# BoardConnector.net
KiCad netlist of a schematic drawn in Altium Designer
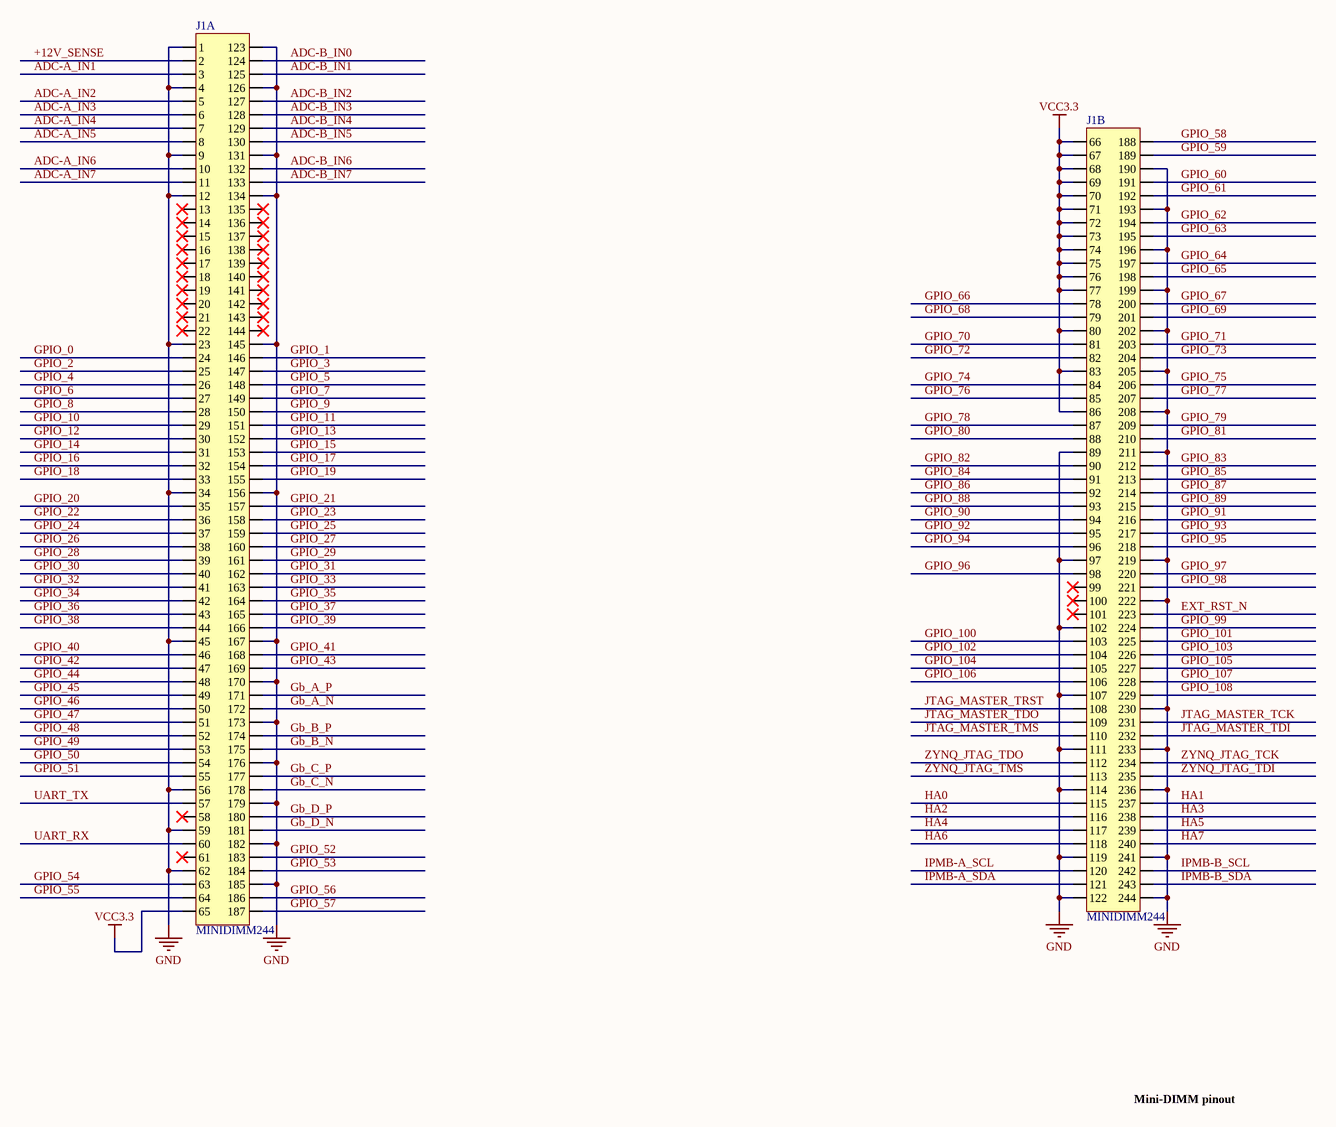
[diagram p0: BoardConnector.SchDoc]

(export (version "E")
  (design (tool "Eeschema 10.0.6"))
  (components
    (comp (ref "J1")
      (value "MINIDIMM244")
      (footprint "miniDIMM244")
      (description "244-pin miniDIMM pads")
      (libsource (lib "CustomParts") (part "MINIDIMM244"))
    )
  )
  (nets
    (net (code "1") (name "/+12V_SENSE") (class "Default")
      (node (ref "J1") (pin "2") (pinfunction "2_2") (pintype "passive"))
    )
    (net (code "2") (name "/ADC-A_IN1") (class "Default")
      (node (ref "J1") (pin "3") (pinfunction "3_3") (pintype "passive"))
    )
    (net (code "3") (name "/ADC-A_IN2") (class "Default")
      (node (ref "J1") (pin "5") (pinfunction "5_5") (pintype "passive"))
    )
    (net (code "4") (name "/ADC-A_IN3") (class "Default")
      (node (ref "J1") (pin "6") (pinfunction "6_6") (pintype "passive"))
    )
    (net (code "5") (name "/ADC-A_IN4") (class "Default")
      (node (ref "J1") (pin "7") (pinfunction "7_7") (pintype "passive"))
    )
    (net (code "6") (name "/ADC-A_IN5") (class "Default")
      (node (ref "J1") (pin "8") (pinfunction "8_8") (pintype "passive"))
    )
    (net (code "7") (name "/ADC-A_IN6") (class "Default")
      (node (ref "J1") (pin "10") (pinfunction "10_10") (pintype "passive"))
    )
    (net (code "8") (name "/ADC-A_IN7") (class "Default")
      (node (ref "J1") (pin "11") (pinfunction "11_11") (pintype "passive"))
    )
    (net (code "9") (name "/ADC-B_IN0") (class "Default")
      (node (ref "J1") (pin "124") (pinfunction "124_124") (pintype "passive"))
    )
    (net (code "10") (name "/ADC-B_IN1") (class "Default")
      (node (ref "J1") (pin "125") (pinfunction "125_125") (pintype "passive"))
    )
    (net (code "11") (name "/ADC-B_IN2") (class "Default")
      (node (ref "J1") (pin "127") (pinfunction "127_127") (pintype "passive"))
    )
    (net (code "12") (name "/ADC-B_IN3") (class "Default")
      (node (ref "J1") (pin "128") (pinfunction "128_128") (pintype "passive"))
    )
    (net (code "13") (name "/ADC-B_IN4") (class "Default")
      (node (ref "J1") (pin "129") (pinfunction "129_129") (pintype "passive"))
    )
    (net (code "14") (name "/ADC-B_IN5") (class "Default")
      (node (ref "J1") (pin "130") (pinfunction "130_130") (pintype "passive"))
    )
    (net (code "15") (name "/ADC-B_IN6") (class "Default")
      (node (ref "J1") (pin "132") (pinfunction "132_132") (pintype "passive"))
    )
    (net (code "16") (name "/ADC-B_IN7") (class "Default")
      (node (ref "J1") (pin "133") (pinfunction "133_133") (pintype "passive"))
    )
    (net (code "17") (name "/EXT_RST_N") (class "Default")
      (node (ref "J1") (pin "223") (pinfunction "223_223") (pintype "passive"))
    )
    (net (code "18") (name "/GPIO_0") (class "Default")
      (node (ref "J1") (pin "24") (pinfunction "24_24") (pintype "passive"))
    )
    (net (code "19") (name "/GPIO_1") (class "Default")
      (node (ref "J1") (pin "146") (pinfunction "146_146") (pintype "passive"))
    )
    (net (code "20") (name "/GPIO_2") (class "Default")
      (node (ref "J1") (pin "25") (pinfunction "25_25") (pintype "passive"))
    )
    (net (code "21") (name "/GPIO_3") (class "Default")
      (node (ref "J1") (pin "147") (pinfunction "147_147") (pintype "passive"))
    )
    (net (code "22") (name "/GPIO_4") (class "Default")
      (node (ref "J1") (pin "26") (pinfunction "26_26") (pintype "passive"))
    )
    (net (code "23") (name "/GPIO_5") (class "Default")
      (node (ref "J1") (pin "148") (pinfunction "148_148") (pintype "passive"))
    )
    (net (code "24") (name "/GPIO_6") (class "Default")
      (node (ref "J1") (pin "27") (pinfunction "27_27") (pintype "passive"))
    )
    (net (code "25") (name "/GPIO_7") (class "Default")
      (node (ref "J1") (pin "149") (pinfunction "149_149") (pintype "passive"))
    )
    (net (code "26") (name "/GPIO_8") (class "Default")
      (node (ref "J1") (pin "28") (pinfunction "28_28") (pintype "passive"))
    )
    (net (code "27") (name "/GPIO_9") (class "Default")
      (node (ref "J1") (pin "150") (pinfunction "150_150") (pintype "passive"))
    )
    (net (code "28") (name "/GPIO_10") (class "Default")
      (node (ref "J1") (pin "29") (pinfunction "29_29") (pintype "passive"))
    )
    (net (code "29") (name "/GPIO_11") (class "Default")
      (node (ref "J1") (pin "151") (pinfunction "151_151") (pintype "passive"))
    )
    (net (code "30") (name "/GPIO_12") (class "Default")
      (node (ref "J1") (pin "30") (pinfunction "30_30") (pintype "passive"))
    )
    (net (code "31") (name "/GPIO_13") (class "Default")
      (node (ref "J1") (pin "152") (pinfunction "152_152") (pintype "passive"))
    )
    (net (code "32") (name "/GPIO_14") (class "Default")
      (node (ref "J1") (pin "31") (pinfunction "31_31") (pintype "passive"))
    )
    (net (code "33") (name "/GPIO_15") (class "Default")
      (node (ref "J1") (pin "153") (pinfunction "153_153") (pintype "passive"))
    )
    (net (code "34") (name "/GPIO_16") (class "Default")
      (node (ref "J1") (pin "32") (pinfunction "32_32") (pintype "passive"))
    )
    (net (code "35") (name "/GPIO_17") (class "Default")
      (node (ref "J1") (pin "154") (pinfunction "154_154") (pintype "passive"))
    )
    (net (code "36") (name "/GPIO_18") (class "Default")
      (node (ref "J1") (pin "33") (pinfunction "33_33") (pintype "passive"))
    )
    (net (code "37") (name "/GPIO_19") (class "Default")
      (node (ref "J1") (pin "155") (pinfunction "155_155") (pintype "passive"))
    )
    (net (code "38") (name "/GPIO_20") (class "Default")
      (node (ref "J1") (pin "35") (pinfunction "35_35") (pintype "passive"))
    )
    (net (code "39") (name "/GPIO_21") (class "Default")
      (node (ref "J1") (pin "157") (pinfunction "157_157") (pintype "passive"))
    )
    (net (code "40") (name "/GPIO_22") (class "Default")
      (node (ref "J1") (pin "36") (pinfunction "36_36") (pintype "passive"))
    )
    (net (code "41") (name "/GPIO_23") (class "Default")
      (node (ref "J1") (pin "158") (pinfunction "158_158") (pintype "passive"))
    )
    (net (code "42") (name "/GPIO_24") (class "Default")
      (node (ref "J1") (pin "37") (pinfunction "37_37") (pintype "passive"))
    )
    (net (code "43") (name "/GPIO_25") (class "Default")
      (node (ref "J1") (pin "159") (pinfunction "159_159") (pintype "passive"))
    )
    (net (code "44") (name "/GPIO_26") (class "Default")
      (node (ref "J1") (pin "38") (pinfunction "38_38") (pintype "passive"))
    )
    (net (code "45") (name "/GPIO_27") (class "Default")
      (node (ref "J1") (pin "160") (pinfunction "160_160") (pintype "passive"))
    )
    (net (code "46") (name "/GPIO_28") (class "Default")
      (node (ref "J1") (pin "39") (pinfunction "39_39") (pintype "passive"))
    )
    (net (code "47") (name "/GPIO_29") (class "Default")
      (node (ref "J1") (pin "161") (pinfunction "161_161") (pintype "passive"))
    )
    (net (code "48") (name "/GPIO_30") (class "Default")
      (node (ref "J1") (pin "40") (pinfunction "40_40") (pintype "passive"))
    )
    (net (code "49") (name "/GPIO_31") (class "Default")
      (node (ref "J1") (pin "162") (pinfunction "162_162") (pintype "passive"))
    )
    (net (code "50") (name "/GPIO_32") (class "Default")
      (node (ref "J1") (pin "41") (pinfunction "41_41") (pintype "passive"))
    )
    (net (code "51") (name "/GPIO_33") (class "Default")
      (node (ref "J1") (pin "163") (pinfunction "163_163") (pintype "passive"))
    )
    (net (code "52") (name "/GPIO_34") (class "Default")
      (node (ref "J1") (pin "42") (pinfunction "42_42") (pintype "passive"))
    )
    (net (code "53") (name "/GPIO_35") (class "Default")
      (node (ref "J1") (pin "164") (pinfunction "164_164") (pintype "passive"))
    )
    (net (code "54") (name "/GPIO_36") (class "Default")
      (node (ref "J1") (pin "43") (pinfunction "43_43") (pintype "passive"))
    )
    (net (code "55") (name "/GPIO_37") (class "Default")
      (node (ref "J1") (pin "165") (pinfunction "165_165") (pintype "passive"))
    )
    (net (code "56") (name "/GPIO_38") (class "Default")
      (node (ref "J1") (pin "44") (pinfunction "44_44") (pintype "passive"))
    )
    (net (code "57") (name "/GPIO_39") (class "Default")
      (node (ref "J1") (pin "166") (pinfunction "166_166") (pintype "passive"))
    )
    (net (code "58") (name "/GPIO_40") (class "Default")
      (node (ref "J1") (pin "46") (pinfunction "46_46") (pintype "passive"))
    )
    (net (code "59") (name "/GPIO_41") (class "Default")
      (node (ref "J1") (pin "168") (pinfunction "168_168") (pintype "passive"))
    )
    (net (code "60") (name "/GPIO_42") (class "Default")
      (node (ref "J1") (pin "47") (pinfunction "47_47") (pintype "passive"))
    )
    (net (code "61") (name "/GPIO_43") (class "Default")
      (node (ref "J1") (pin "169") (pinfunction "169_169") (pintype "passive"))
    )
    (net (code "62") (name "/GPIO_44") (class "Default")
      (node (ref "J1") (pin "48") (pinfunction "48_48") (pintype "passive"))
    )
    (net (code "63") (name "/GPIO_45") (class "Default")
      (node (ref "J1") (pin "49") (pinfunction "49_49") (pintype "passive"))
    )
    (net (code "64") (name "/GPIO_46") (class "Default")
      (node (ref "J1") (pin "50") (pinfunction "50_50") (pintype "passive"))
    )
    (net (code "65") (name "/GPIO_47") (class "Default")
      (node (ref "J1") (pin "51") (pinfunction "51_51") (pintype "passive"))
    )
    (net (code "66") (name "/GPIO_48") (class "Default")
      (node (ref "J1") (pin "52") (pinfunction "52_52") (pintype "passive"))
    )
    (net (code "67") (name "/GPIO_49") (class "Default")
      (node (ref "J1") (pin "53") (pinfunction "53_53") (pintype "passive"))
    )
    (net (code "68") (name "/GPIO_50") (class "Default")
      (node (ref "J1") (pin "54") (pinfunction "54_54") (pintype "passive"))
    )
    (net (code "69") (name "/GPIO_51") (class "Default")
      (node (ref "J1") (pin "55") (pinfunction "55_55") (pintype "passive"))
    )
    (net (code "70") (name "/GPIO_52") (class "Default")
      (node (ref "J1") (pin "183") (pinfunction "183_183") (pintype "passive"))
    )
    (net (code "71") (name "/GPIO_53") (class "Default")
      (node (ref "J1") (pin "184") (pinfunction "184_184") (pintype "passive"))
    )
    (net (code "72") (name "/GPIO_54") (class "Default")
      (node (ref "J1") (pin "63") (pinfunction "63_63") (pintype "passive"))
    )
    (net (code "73") (name "/GPIO_55") (class "Default")
      (node (ref "J1") (pin "64") (pinfunction "64_64") (pintype "passive"))
    )
    (net (code "74") (name "/GPIO_56") (class "Default")
      (node (ref "J1") (pin "186") (pinfunction "186_186") (pintype "passive"))
    )
    (net (code "75") (name "/GPIO_57") (class "Default")
      (node (ref "J1") (pin "187") (pinfunction "187_187") (pintype "passive"))
    )
    (net (code "76") (name "/GPIO_58") (class "Default")
      (node (ref "J1") (pin "188") (pinfunction "188_188") (pintype "passive"))
    )
    (net (code "77") (name "/GPIO_59") (class "Default")
      (node (ref "J1") (pin "189") (pinfunction "189_189") (pintype "passive"))
    )
    (net (code "78") (name "/GPIO_60") (class "Default")
      (node (ref "J1") (pin "191") (pinfunction "191_191") (pintype "passive"))
    )
    (net (code "79") (name "/GPIO_61") (class "Default")
      (node (ref "J1") (pin "192") (pinfunction "192_192") (pintype "passive"))
    )
    (net (code "80") (name "/GPIO_62") (class "Default")
      (node (ref "J1") (pin "194") (pinfunction "194_194") (pintype "passive"))
    )
    (net (code "81") (name "/GPIO_63") (class "Default")
      (node (ref "J1") (pin "195") (pinfunction "195_195") (pintype "passive"))
    )
    (net (code "82") (name "/GPIO_64") (class "Default")
      (node (ref "J1") (pin "197") (pinfunction "197_197") (pintype "passive"))
    )
    (net (code "83") (name "/GPIO_65") (class "Default")
      (node (ref "J1") (pin "198") (pinfunction "198_198") (pintype "passive"))
    )
    (net (code "84") (name "/GPIO_66") (class "Default")
      (node (ref "J1") (pin "78") (pinfunction "78_78") (pintype "passive"))
    )
    (net (code "85") (name "/GPIO_67") (class "Default")
      (node (ref "J1") (pin "200") (pinfunction "200_200") (pintype "passive"))
    )
    (net (code "86") (name "/GPIO_68") (class "Default")
      (node (ref "J1") (pin "79") (pinfunction "79_79") (pintype "passive"))
    )
    (net (code "87") (name "/GPIO_69") (class "Default")
      (node (ref "J1") (pin "201") (pinfunction "201_201") (pintype "passive"))
    )
    (net (code "88") (name "/GPIO_70") (class "Default")
      (node (ref "J1") (pin "81") (pinfunction "81_81") (pintype "passive"))
    )
    (net (code "89") (name "/GPIO_71") (class "Default")
      (node (ref "J1") (pin "203") (pinfunction "203_203") (pintype "passive"))
    )
    (net (code "90") (name "/GPIO_72") (class "Default")
      (node (ref "J1") (pin "82") (pinfunction "82_82") (pintype "passive"))
    )
    (net (code "91") (name "/GPIO_73") (class "Default")
      (node (ref "J1") (pin "204") (pinfunction "204_204") (pintype "passive"))
    )
    (net (code "92") (name "/GPIO_74") (class "Default")
      (node (ref "J1") (pin "84") (pinfunction "84_84") (pintype "passive"))
    )
    (net (code "93") (name "/GPIO_75") (class "Default")
      (node (ref "J1") (pin "206") (pinfunction "206_206") (pintype "passive"))
    )
    (net (code "94") (name "/GPIO_76") (class "Default")
      (node (ref "J1") (pin "85") (pinfunction "85_85") (pintype "passive"))
    )
    (net (code "95") (name "/GPIO_77") (class "Default")
      (node (ref "J1") (pin "207") (pinfunction "207_207") (pintype "passive"))
    )
    (net (code "96") (name "/GPIO_78") (class "Default")
      (node (ref "J1") (pin "87") (pinfunction "87_87") (pintype "passive"))
    )
    (net (code "97") (name "/GPIO_79") (class "Default")
      (node (ref "J1") (pin "209") (pinfunction "209_209") (pintype "passive"))
    )
    (net (code "98") (name "/GPIO_80") (class "Default")
      (node (ref "J1") (pin "88") (pinfunction "88_88") (pintype "passive"))
    )
    (net (code "99") (name "/GPIO_81") (class "Default")
      (node (ref "J1") (pin "210") (pinfunction "210_210") (pintype "passive"))
    )
    (net (code "100") (name "/GPIO_82") (class "Default")
      (node (ref "J1") (pin "90") (pinfunction "90_90") (pintype "passive"))
    )
    (net (code "101") (name "/GPIO_83") (class "Default")
      (node (ref "J1") (pin "212") (pinfunction "212_212") (pintype "passive"))
    )
    (net (code "102") (name "/GPIO_84") (class "Default")
      (node (ref "J1") (pin "91") (pinfunction "91_91") (pintype "passive"))
    )
    (net (code "103") (name "/GPIO_85") (class "Default")
      (node (ref "J1") (pin "213") (pinfunction "213_213") (pintype "passive"))
    )
    (net (code "104") (name "/GPIO_86") (class "Default")
      (node (ref "J1") (pin "92") (pinfunction "92_92") (pintype "passive"))
    )
    (net (code "105") (name "/GPIO_87") (class "Default")
      (node (ref "J1") (pin "214") (pinfunction "214_214") (pintype "passive"))
    )
    (net (code "106") (name "/GPIO_88") (class "Default")
      (node (ref "J1") (pin "93") (pinfunction "93_93") (pintype "passive"))
    )
    (net (code "107") (name "/GPIO_89") (class "Default")
      (node (ref "J1") (pin "215") (pinfunction "215_215") (pintype "passive"))
    )
    (net (code "108") (name "/GPIO_90") (class "Default")
      (node (ref "J1") (pin "94") (pinfunction "94_94") (pintype "passive"))
    )
    (net (code "109") (name "/GPIO_91") (class "Default")
      (node (ref "J1") (pin "216") (pinfunction "216_216") (pintype "passive"))
    )
    (net (code "110") (name "/GPIO_92") (class "Default")
      (node (ref "J1") (pin "95") (pinfunction "95_95") (pintype "passive"))
    )
    (net (code "111") (name "/GPIO_93") (class "Default")
      (node (ref "J1") (pin "217") (pinfunction "217_217") (pintype "passive"))
    )
    (net (code "112") (name "/GPIO_94") (class "Default")
      (node (ref "J1") (pin "96") (pinfunction "96_96") (pintype "passive"))
    )
    (net (code "113") (name "/GPIO_95") (class "Default")
      (node (ref "J1") (pin "218") (pinfunction "218_218") (pintype "passive"))
    )
    (net (code "114") (name "/GPIO_96") (class "Default")
      (node (ref "J1") (pin "98") (pinfunction "98_98") (pintype "passive"))
    )
    (net (code "115") (name "/GPIO_97") (class "Default")
      (node (ref "J1") (pin "220") (pinfunction "220_220") (pintype "passive"))
    )
    (net (code "116") (name "/GPIO_98") (class "Default")
      (node (ref "J1") (pin "221") (pinfunction "221_221") (pintype "passive"))
    )
    (net (code "117") (name "/GPIO_99") (class "Default")
      (node (ref "J1") (pin "224") (pinfunction "224_224") (pintype "passive"))
    )
    (net (code "118") (name "/GPIO_100") (class "Default")
      (node (ref "J1") (pin "103") (pinfunction "103_103") (pintype "passive"))
    )
    (net (code "119") (name "/GPIO_101") (class "Default")
      (node (ref "J1") (pin "225") (pinfunction "225_225") (pintype "passive"))
    )
    (net (code "120") (name "/GPIO_102") (class "Default")
      (node (ref "J1") (pin "104") (pinfunction "104_104") (pintype "passive"))
    )
    (net (code "121") (name "/GPIO_103") (class "Default")
      (node (ref "J1") (pin "226") (pinfunction "226_226") (pintype "passive"))
    )
    (net (code "122") (name "/GPIO_104") (class "Default")
      (node (ref "J1") (pin "105") (pinfunction "105_105") (pintype "passive"))
    )
    (net (code "123") (name "/GPIO_105") (class "Default")
      (node (ref "J1") (pin "227") (pinfunction "227_227") (pintype "passive"))
    )
    (net (code "124") (name "/GPIO_106") (class "Default")
      (node (ref "J1") (pin "106") (pinfunction "106_106") (pintype "passive"))
    )
    (net (code "125") (name "/GPIO_107") (class "Default")
      (node (ref "J1") (pin "228") (pinfunction "228_228") (pintype "passive"))
    )
    (net (code "126") (name "/GPIO_108") (class "Default")
      (node (ref "J1") (pin "229") (pinfunction "229_229") (pintype "passive"))
    )
    (net (code "127") (name "/Gb_A_N") (class "Default")
      (node (ref "J1") (pin "172") (pinfunction "172_172") (pintype "passive"))
    )
    (net (code "128") (name "/Gb_A_P") (class "Default")
      (node (ref "J1") (pin "171") (pinfunction "171_171") (pintype "passive"))
    )
    (net (code "129") (name "/Gb_B_N") (class "Default")
      (node (ref "J1") (pin "175") (pinfunction "175_175") (pintype "passive"))
    )
    (net (code "130") (name "/Gb_B_P") (class "Default")
      (node (ref "J1") (pin "174") (pinfunction "174_174") (pintype "passive"))
    )
    (net (code "131") (name "/Gb_C_N") (class "Default")
      (node (ref "J1") (pin "178") (pinfunction "178_178") (pintype "passive"))
    )
    (net (code "132") (name "/Gb_C_P") (class "Default")
      (node (ref "J1") (pin "177") (pinfunction "177_177") (pintype "passive"))
    )
    (net (code "133") (name "/Gb_D_N") (class "Default")
      (node (ref "J1") (pin "181") (pinfunction "181_181") (pintype "passive"))
    )
    (net (code "134") (name "/Gb_D_P") (class "Default")
      (node (ref "J1") (pin "180") (pinfunction "180_180") (pintype "passive"))
    )
    (net (code "135") (name "/HA0") (class "Default")
      (node (ref "J1") (pin "115") (pinfunction "115_115") (pintype "passive"))
    )
    (net (code "136") (name "/HA1") (class "Default")
      (node (ref "J1") (pin "237") (pinfunction "237_237") (pintype "passive"))
    )
    (net (code "137") (name "/HA2") (class "Default")
      (node (ref "J1") (pin "116") (pinfunction "116_116") (pintype "passive"))
    )
    (net (code "138") (name "/HA3") (class "Default")
      (node (ref "J1") (pin "238") (pinfunction "238_238") (pintype "passive"))
    )
    (net (code "139") (name "/HA4") (class "Default")
      (node (ref "J1") (pin "117") (pinfunction "117_117") (pintype "passive"))
    )
    (net (code "140") (name "/HA5") (class "Default")
      (node (ref "J1") (pin "239") (pinfunction "239_239") (pintype "passive"))
    )
    (net (code "141") (name "/HA6") (class "Default")
      (node (ref "J1") (pin "118") (pinfunction "118_118") (pintype "passive"))
    )
    (net (code "142") (name "/HA7") (class "Default")
      (node (ref "J1") (pin "240") (pinfunction "240_240") (pintype "passive"))
    )
    (net (code "143") (name "/IPMB-A_SCL") (class "Default")
      (node (ref "J1") (pin "120") (pinfunction "120_120") (pintype "passive"))
    )
    (net (code "144") (name "/IPMB-A_SDA") (class "Default")
      (node (ref "J1") (pin "121") (pinfunction "121_121") (pintype "passive"))
    )
    (net (code "145") (name "/IPMB-B_SCL") (class "Default")
      (node (ref "J1") (pin "242") (pinfunction "242_242") (pintype "passive"))
    )
    (net (code "146") (name "/IPMB-B_SDA") (class "Default")
      (node (ref "J1") (pin "243") (pinfunction "243_243") (pintype "passive"))
    )
    (net (code "147") (name "/JTAG_MASTER_TCK") (class "Default")
      (node (ref "J1") (pin "231") (pinfunction "231_231") (pintype "passive"))
    )
    (net (code "148") (name "/JTAG_MASTER_TDI") (class "Default")
      (node (ref "J1") (pin "232") (pinfunction "232_232") (pintype "passive"))
    )
    (net (code "149") (name "/JTAG_MASTER_TDO") (class "Default")
      (node (ref "J1") (pin "109") (pinfunction "109_109") (pintype "passive"))
    )
    (net (code "150") (name "/JTAG_MASTER_TMS") (class "Default")
      (node (ref "J1") (pin "110") (pinfunction "110_110") (pintype "passive"))
    )
    (net (code "151") (name "/JTAG_MASTER_TRST") (class "Default")
      (node (ref "J1") (pin "108") (pinfunction "108_108") (pintype "passive"))
    )
    (net (code "152") (name "/UART_RX") (class "Default")
      (node (ref "J1") (pin "60") (pinfunction "60_60") (pintype "passive"))
    )
    (net (code "153") (name "/UART_TX") (class "Default")
      (node (ref "J1") (pin "57") (pinfunction "57_57") (pintype "passive"))
    )
    (net (code "154") (name "/ZYNQ_JTAG_TCK") (class "Default")
      (node (ref "J1") (pin "234") (pinfunction "234_234") (pintype "passive"))
    )
    (net (code "155") (name "/ZYNQ_JTAG_TDI") (class "Default")
      (node (ref "J1") (pin "235") (pinfunction "235_235") (pintype "passive"))
    )
    (net (code "156") (name "/ZYNQ_JTAG_TDO") (class "Default")
      (node (ref "J1") (pin "112") (pinfunction "112_112") (pintype "passive"))
    )
    (net (code "157") (name "/ZYNQ_JTAG_TMS") (class "Default")
      (node (ref "J1") (pin "113") (pinfunction "113_113") (pintype "passive"))
    )
    (net (code "158") (name "GND") (class "Default")
      (node (ref "J1") (pin "1") (pinfunction "1_1") (pintype "passive"))
      (node (ref "J1") (pin "102") (pinfunction "102_102") (pintype "passive"))
      (node (ref "J1") (pin "107") (pinfunction "107_107") (pintype "passive"))
      (node (ref "J1") (pin "111") (pinfunction "111_111") (pintype "passive"))
      (node (ref "J1") (pin "114") (pinfunction "114_114") (pintype "passive"))
      (node (ref "J1") (pin "119") (pinfunction "119_119") (pintype "passive"))
      (node (ref "J1") (pin "12") (pinfunction "12_12") (pintype "passive"))
      (node (ref "J1") (pin "122") (pinfunction "122_122") (pintype "passive"))
      (node (ref "J1") (pin "123") (pinfunction "123_123") (pintype "passive"))
      (node (ref "J1") (pin "126") (pinfunction "126_126") (pintype "passive"))
      (node (ref "J1") (pin "131") (pinfunction "131_131") (pintype "passive"))
      (node (ref "J1") (pin "134") (pinfunction "134_134") (pintype "passive"))
      (node (ref "J1") (pin "145") (pinfunction "145_145") (pintype "passive"))
      (node (ref "J1") (pin "156") (pinfunction "156_156") (pintype "passive"))
      (node (ref "J1") (pin "167") (pinfunction "167_167") (pintype "passive"))
      (node (ref "J1") (pin "170") (pinfunction "170_170") (pintype "passive"))
      (node (ref "J1") (pin "173") (pinfunction "173_173") (pintype "passive"))
      (node (ref "J1") (pin "176") (pinfunction "176_176") (pintype "passive"))
      (node (ref "J1") (pin "179") (pinfunction "179_179") (pintype "passive"))
      (node (ref "J1") (pin "182") (pinfunction "182_182") (pintype "passive"))
      (node (ref "J1") (pin "185") (pinfunction "185_185") (pintype "passive"))
      (node (ref "J1") (pin "190") (pinfunction "190_190") (pintype "passive"))
      (node (ref "J1") (pin "193") (pinfunction "193_193") (pintype "passive"))
      (node (ref "J1") (pin "196") (pinfunction "196_196") (pintype "passive"))
      (node (ref "J1") (pin "199") (pinfunction "199_199") (pintype "passive"))
      (node (ref "J1") (pin "202") (pinfunction "202_202") (pintype "passive"))
      (node (ref "J1") (pin "205") (pinfunction "205_205") (pintype "passive"))
      (node (ref "J1") (pin "208") (pinfunction "208_208") (pintype "passive"))
      (node (ref "J1") (pin "211") (pinfunction "211_211") (pintype "passive"))
      (node (ref "J1") (pin "219") (pinfunction "219_219") (pintype "passive"))
      (node (ref "J1") (pin "222") (pinfunction "222_222") (pintype "passive"))
      (node (ref "J1") (pin "23") (pinfunction "23_23") (pintype "passive"))
      (node (ref "J1") (pin "230") (pinfunction "230_230") (pintype "passive"))
      (node (ref "J1") (pin "233") (pinfunction "233_233") (pintype "passive"))
      (node (ref "J1") (pin "236") (pinfunction "236_236") (pintype "passive"))
      (node (ref "J1") (pin "241") (pinfunction "241_241") (pintype "passive"))
      (node (ref "J1") (pin "244") (pinfunction "244_244") (pintype "passive"))
      (node (ref "J1") (pin "34") (pinfunction "34_34") (pintype "passive"))
      (node (ref "J1") (pin "4") (pinfunction "4_4") (pintype "passive"))
      (node (ref "J1") (pin "45") (pinfunction "45_45") (pintype "passive"))
      (node (ref "J1") (pin "56") (pinfunction "56_56") (pintype "passive"))
      (node (ref "J1") (pin "59") (pinfunction "59_59") (pintype "passive"))
      (node (ref "J1") (pin "62") (pinfunction "62_62") (pintype "passive"))
      (node (ref "J1") (pin "89") (pinfunction "89_89") (pintype "passive"))
      (node (ref "J1") (pin "9") (pinfunction "9_9") (pintype "passive"))
      (node (ref "J1") (pin "97") (pinfunction "97_97") (pintype "passive"))
    )
    (net (code "159") (name "VCC3.3") (class "Default")
      (node (ref "J1") (pin "65") (pinfunction "65_65") (pintype "passive"))
      (node (ref "J1") (pin "66") (pinfunction "66_66") (pintype "passive"))
      (node (ref "J1") (pin "67") (pinfunction "67_67") (pintype "passive"))
      (node (ref "J1") (pin "68") (pinfunction "68_68") (pintype "passive"))
      (node (ref "J1") (pin "69") (pinfunction "69_69") (pintype "passive"))
      (node (ref "J1") (pin "70") (pinfunction "70_70") (pintype "passive"))
      (node (ref "J1") (pin "71") (pinfunction "71_71") (pintype "passive"))
      (node (ref "J1") (pin "72") (pinfunction "72_72") (pintype "passive"))
      (node (ref "J1") (pin "73") (pinfunction "73_73") (pintype "passive"))
      (node (ref "J1") (pin "74") (pinfunction "74_74") (pintype "passive"))
      (node (ref "J1") (pin "75") (pinfunction "75_75") (pintype "passive"))
      (node (ref "J1") (pin "76") (pinfunction "76_76") (pintype "passive"))
      (node (ref "J1") (pin "77") (pinfunction "77_77") (pintype "passive"))
      (node (ref "J1") (pin "80") (pinfunction "80_80") (pintype "passive"))
      (node (ref "J1") (pin "83") (pinfunction "83_83") (pintype "passive"))
      (node (ref "J1") (pin "86") (pinfunction "86_86") (pintype "passive"))
    )
    (net (code "160") (name "unconnected-(J1-Pad13)") (class "Default")
      (node (ref "J1") (pin "13") (pinfunction "13_13") (pintype "passive+no_connect"))
    )
    (net (code "161") (name "unconnected-(J1-Pad14)") (class "Default")
      (node (ref "J1") (pin "14") (pinfunction "14_14") (pintype "passive+no_connect"))
    )
    (net (code "162") (name "unconnected-(J1-Pad15)") (class "Default")
      (node (ref "J1") (pin "15") (pinfunction "15_15") (pintype "passive+no_connect"))
    )
    (net (code "163") (name "unconnected-(J1-Pad16)") (class "Default")
      (node (ref "J1") (pin "16") (pinfunction "16_16") (pintype "passive+no_connect"))
    )
    (net (code "164") (name "unconnected-(J1-Pad17)") (class "Default")
      (node (ref "J1") (pin "17") (pinfunction "17_17") (pintype "passive+no_connect"))
    )
    (net (code "165") (name "unconnected-(J1-Pad18)") (class "Default")
      (node (ref "J1") (pin "18") (pinfunction "18_18") (pintype "passive+no_connect"))
    )
    (net (code "166") (name "unconnected-(J1-Pad19)") (class "Default")
      (node (ref "J1") (pin "19") (pinfunction "19_19") (pintype "passive+no_connect"))
    )
    (net (code "167") (name "unconnected-(J1-Pad20)") (class "Default")
      (node (ref "J1") (pin "20") (pinfunction "20_20") (pintype "passive+no_connect"))
    )
    (net (code "168") (name "unconnected-(J1-Pad21)") (class "Default")
      (node (ref "J1") (pin "21") (pinfunction "21_21") (pintype "passive+no_connect"))
    )
    (net (code "169") (name "unconnected-(J1-Pad22)") (class "Default")
      (node (ref "J1") (pin "22") (pinfunction "22_22") (pintype "passive+no_connect"))
    )
    (net (code "170") (name "unconnected-(J1-Pad58)") (class "Default")
      (node (ref "J1") (pin "58") (pinfunction "58_58") (pintype "passive+no_connect"))
    )
    (net (code "171") (name "unconnected-(J1-Pad61)") (class "Default")
      (node (ref "J1") (pin "61") (pinfunction "61_61") (pintype "passive+no_connect"))
    )
    (net (code "172") (name "unconnected-(J1-Pad99)") (class "Default")
      (node (ref "J1") (pin "99") (pinfunction "99_99") (pintype "passive+no_connect"))
    )
    (net (code "173") (name "unconnected-(J1-Pad100)") (class "Default")
      (node (ref "J1") (pin "100") (pinfunction "100_100") (pintype "passive+no_connect"))
    )
    (net (code "174") (name "unconnected-(J1-Pad101)") (class "Default")
      (node (ref "J1") (pin "101") (pinfunction "101_101") (pintype "passive+no_connect"))
    )
    (net (code "175") (name "unconnected-(J1-Pad135)") (class "Default")
      (node (ref "J1") (pin "135") (pinfunction "135_135") (pintype "passive+no_connect"))
    )
    (net (code "176") (name "unconnected-(J1-Pad136)") (class "Default")
      (node (ref "J1") (pin "136") (pinfunction "136_136") (pintype "passive+no_connect"))
    )
    (net (code "177") (name "unconnected-(J1-Pad137)") (class "Default")
      (node (ref "J1") (pin "137") (pinfunction "137_137") (pintype "passive+no_connect"))
    )
    (net (code "178") (name "unconnected-(J1-Pad138)") (class "Default")
      (node (ref "J1") (pin "138") (pinfunction "138_138") (pintype "passive+no_connect"))
    )
    (net (code "179") (name "unconnected-(J1-Pad139)") (class "Default")
      (node (ref "J1") (pin "139") (pinfunction "139_139") (pintype "passive+no_connect"))
    )
    (net (code "180") (name "unconnected-(J1-Pad140)") (class "Default")
      (node (ref "J1") (pin "140") (pinfunction "140_140") (pintype "passive+no_connect"))
    )
    (net (code "181") (name "unconnected-(J1-Pad141)") (class "Default")
      (node (ref "J1") (pin "141") (pinfunction "141_141") (pintype "passive+no_connect"))
    )
    (net (code "182") (name "unconnected-(J1-Pad142)") (class "Default")
      (node (ref "J1") (pin "142") (pinfunction "142_142") (pintype "passive+no_connect"))
    )
    (net (code "183") (name "unconnected-(J1-Pad143)") (class "Default")
      (node (ref "J1") (pin "143") (pinfunction "143_143") (pintype "passive+no_connect"))
    )
    (net (code "184") (name "unconnected-(J1-Pad144)") (class "Default")
      (node (ref "J1") (pin "144") (pinfunction "144_144") (pintype "passive+no_connect"))
    )
  )
)
